# 140629_AriloTX_REV2_0_0.net
KiCad netlist of a schematic drawn in EAGLE
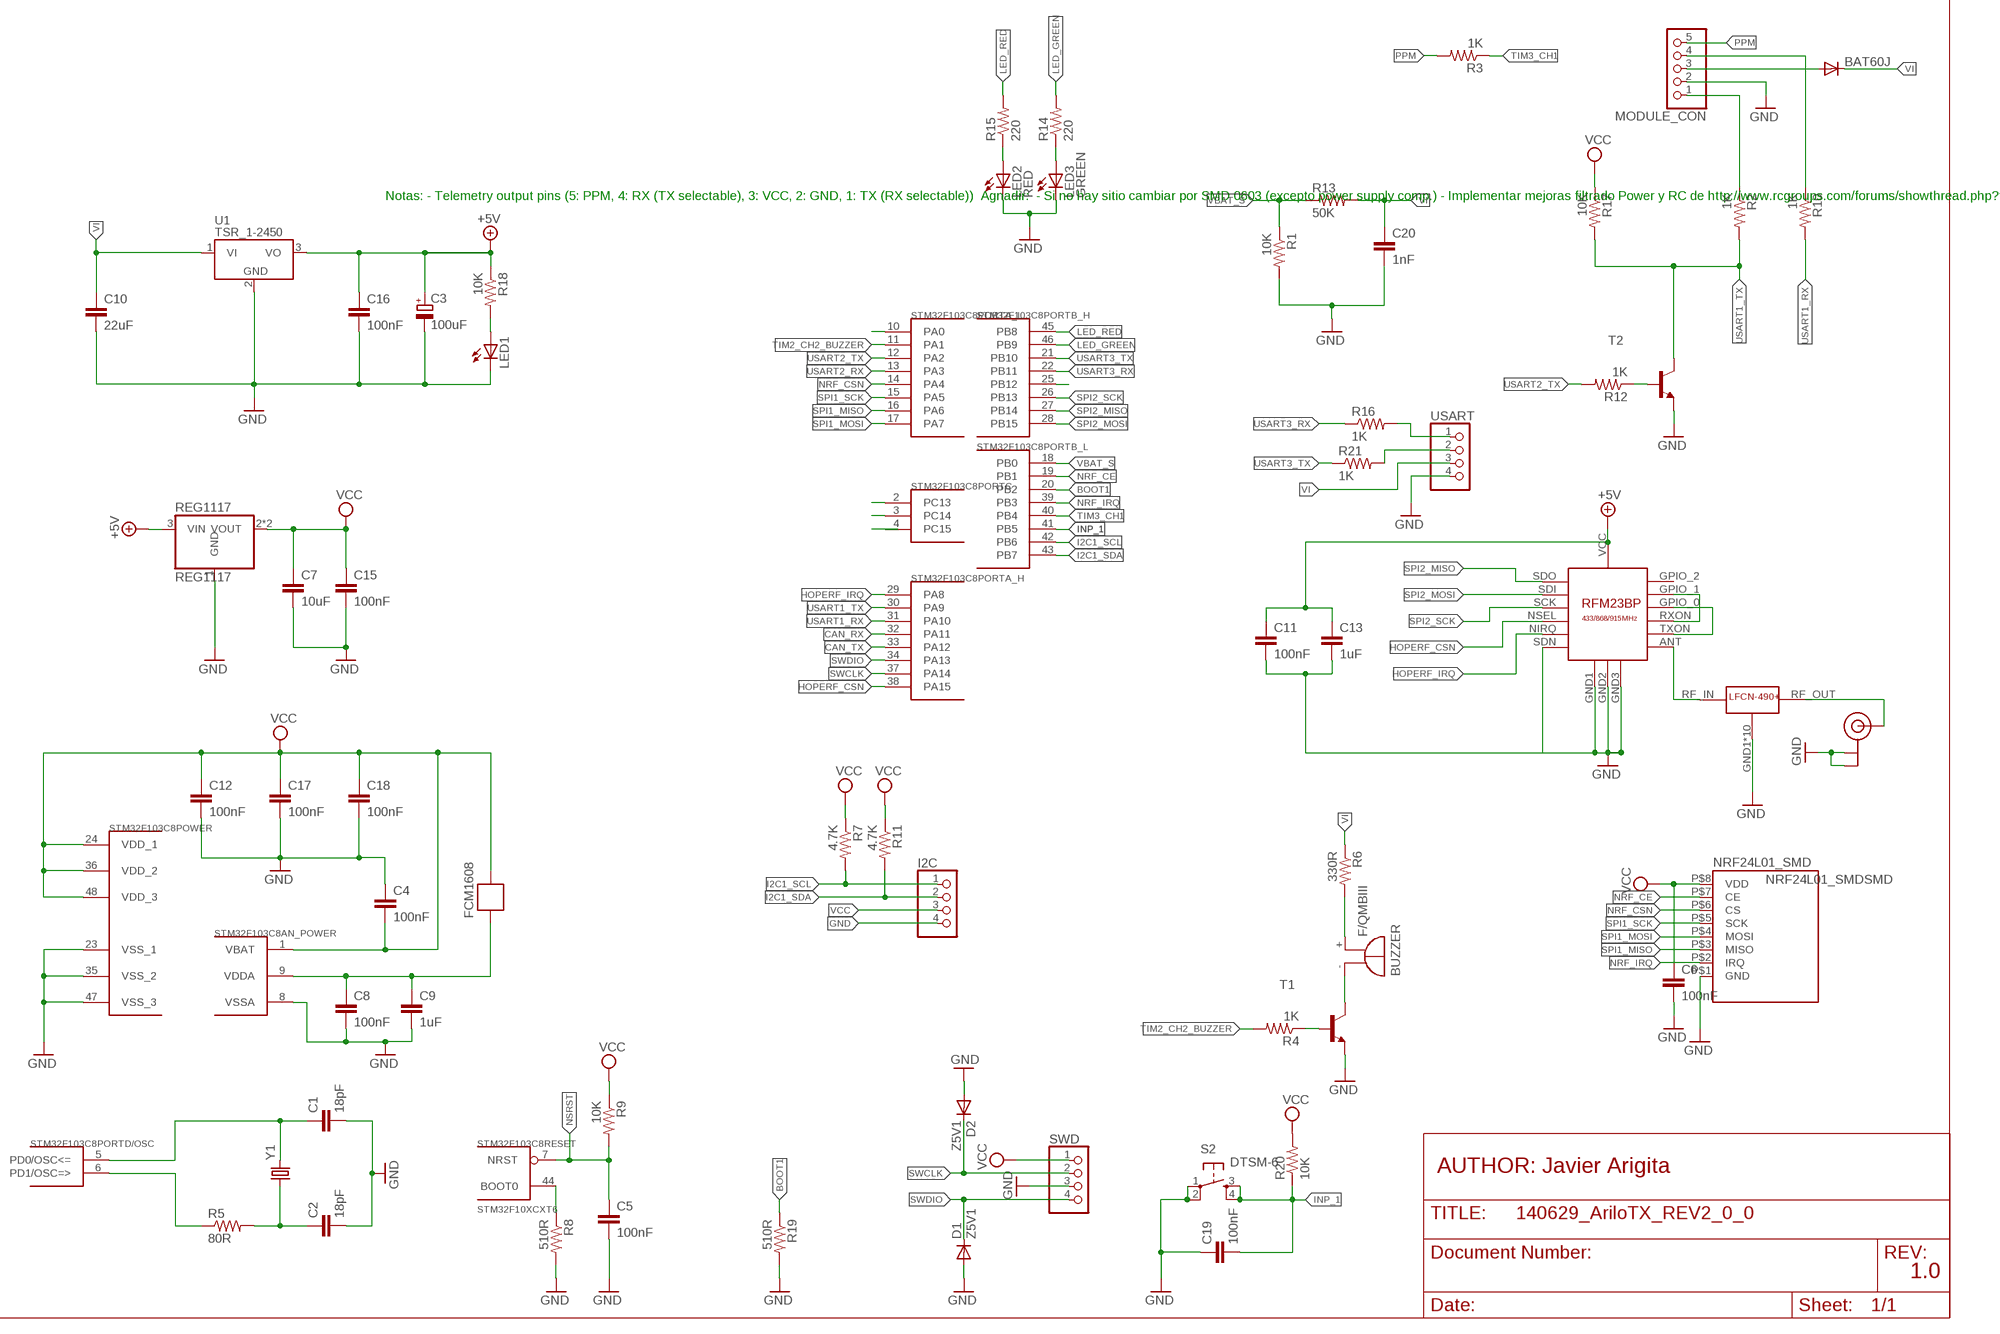
[diagram p0: schematic, sheet 1, part 1 of 2]
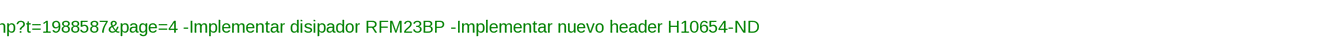
[diagram p1: schematic, sheet 1, part 2 of 2]

(export (version "E")
  (design (tool "Eeschema 10.0.6"))
  (components
    (comp (ref "BAT60J")
      (value "DIODE-SOD323-R")
      (footprint "eagle-import:SOD323-R")
      (libsource (lib "eagle-import") (part "DIODE-SOD323-R"))
    )
    (comp (ref "BUZZER")
      (value "F/QMBIII")
      (footprint "eagle-import:F_QMBIII")
      (libsource (lib "eagle-import") (part "F/QMBIII"))
    )
    (comp (ref "C1")
      (value "18pF")
      (footprint "eagle-import:C0805")
      (libsource (lib "eagle-import") (part "C-EUC0805"))
    )
    (comp (ref "C2")
      (value "18pF")
      (footprint "eagle-import:C0805")
      (libsource (lib "eagle-import") (part "C-EUC0805"))
    )
    (comp (ref "C3")
      (value "100uF")
      (footprint "eagle-import:SMC_B")
      (libsource (lib "eagle-import") (part "CPOL-EUSMCB"))
    )
    (comp (ref "C4")
      (value "100nF")
      (footprint "eagle-import:C0805")
      (libsource (lib "eagle-import") (part "C-EUC0805"))
    )
    (comp (ref "C5")
      (value "100nF")
      (footprint "eagle-import:C0805")
      (libsource (lib "eagle-import") (part "C-EUC0805"))
    )
    (comp (ref "C6")
      (value "100nF")
      (footprint "eagle-import:C0805")
      (libsource (lib "eagle-import") (part "C-EUC0805"))
    )
    (comp (ref "C7")
      (value "10uF")
      (footprint "eagle-import:C0805")
      (libsource (lib "eagle-import") (part "C-EUC0805"))
    )
    (comp (ref "C8")
      (value "100nF")
      (footprint "eagle-import:C0805")
      (libsource (lib "eagle-import") (part "C-EUC0805"))
    )
    (comp (ref "C9")
      (value "1uF")
      (footprint "eagle-import:C3216")
      (libsource (lib "eagle-import") (part "resistor_C-EUC3216"))
    )
    (comp (ref "C10")
      (value "22uF")
      (footprint "eagle-import:C3216")
      (libsource (lib "eagle-import") (part "resistor_C-EUC3216"))
    )
    (comp (ref "C11")
      (value "100nF")
      (footprint "eagle-import:C0805")
      (libsource (lib "eagle-import") (part "C-EUC0805"))
    )
    (comp (ref "C12")
      (value "100nF")
      (footprint "eagle-import:C0805")
      (libsource (lib "eagle-import") (part "C-EUC0805"))
    )
    (comp (ref "C13")
      (value "1uF")
      (footprint "eagle-import:C3216")
      (libsource (lib "eagle-import") (part "resistor_C-EUC3216"))
    )
    (comp (ref "C15")
      (value "100nF")
      (footprint "eagle-import:C0805")
      (libsource (lib "eagle-import") (part "C-EUC0805"))
    )
    (comp (ref "C16")
      (value "100nF")
      (footprint "eagle-import:C0805")
      (libsource (lib "eagle-import") (part "C-EUC0805"))
    )
    (comp (ref "C17")
      (value "100nF")
      (footprint "eagle-import:C0805")
      (libsource (lib "eagle-import") (part "C-EUC0805"))
    )
    (comp (ref "C18")
      (value "100nF")
      (footprint "eagle-import:C0805")
      (libsource (lib "eagle-import") (part "C-EUC0805"))
    )
    (comp (ref "C19")
      (value "100nF")
      (footprint "eagle-import:C0805")
      (libsource (lib "eagle-import") (part "C-EUC0805"))
    )
    (comp (ref "C20")
      (value "1nF")
      (footprint "eagle-import:C0805")
      (libsource (lib "eagle-import") (part "C-EUC0805"))
    )
    (comp (ref "D1")
      (value "Z5V1")
      (footprint "eagle-import:SOD323-R")
      (libsource (lib "eagle-import") (part "DIODE-SOD323-R"))
    )
    (comp (ref "D2")
      (value "Z5V1")
      (footprint "eagle-import:SOD323-R")
      (libsource (lib "eagle-import") (part "DIODE-SOD323-R"))
    )
    (comp (ref "FCM1608")
      (value "FERRITE-BEAD")
      (footprint "eagle-import:R0603")
      (libsource (lib "eagle-import") (part "FERRITE-BEAD"))
    )
    (comp (ref "I2C")
      (value "PINHD-1X4")
      (footprint "eagle-import:1X04")
      (libsource (lib "eagle-import") (part "PINHD-1X4"))
    )
    (comp (ref "LED1")
      (value "LED0805")
      (footprint "eagle-import:CHIPLED_0805")
      (libsource (lib "eagle-import") (part "LED0805"))
    )
    (comp (ref "LED2")
      (value "RED")
      (footprint "eagle-import:CHIP-LED0805")
      (libsource (lib "eagle-import") (part "LEDCHIP-LED0805"))
    )
    (comp (ref "LED3")
      (value "GREEN")
      (footprint "eagle-import:CHIP-LED0805")
      (libsource (lib "eagle-import") (part "LEDCHIP-LED0805"))
    )
    (comp (ref "MODULE_CON")
      (value "PINHD-1X5")
      (footprint "eagle-import:1X05")
      (libsource (lib "eagle-import") (part "PINHD-1X5"))
    )
    (comp (ref "NRF24L01_SMD")
      (value "NRF24L01_SMDSMD")
      (footprint "eagle-import:NRF24L01_SMD")
      (libsource (lib "eagle-import") (part "NRF24L01_SMDSMD"))
    )
    (comp (ref "R1")
      (value "10K")
      (footprint "eagle-import:R0805")
      (libsource (lib "eagle-import") (part "RESISTOR0805"))
    )
    (comp (ref "R2")
      (value "1K")
      (footprint "eagle-import:R0805")
      (libsource (lib "eagle-import") (part "RESISTOR0805"))
    )
    (comp (ref "R3")
      (value "1K")
      (footprint "eagle-import:R0805")
      (libsource (lib "eagle-import") (part "RESISTOR0805"))
    )
    (comp (ref "R4")
      (value "1K")
      (footprint "eagle-import:R0805")
      (libsource (lib "eagle-import") (part "RESISTOR0805"))
    )
    (comp (ref "R5")
      (value "80R")
      (footprint "eagle-import:R0805")
      (libsource (lib "eagle-import") (part "RESISTOR0805"))
    )
    (comp (ref "R6")
      (value "330R")
      (footprint "eagle-import:R0805")
      (libsource (lib "eagle-import") (part "RESISTOR0805"))
    )
    (comp (ref "R7")
      (value "4.7K")
      (footprint "eagle-import:R0805")
      (libsource (lib "eagle-import") (part "RESISTOR0805"))
    )
    (comp (ref "R8")
      (value "510R")
      (footprint "eagle-import:R0805")
      (libsource (lib "eagle-import") (part "RESISTOR0805"))
    )
    (comp (ref "R9")
      (value "10K")
      (footprint "eagle-import:R0805")
      (libsource (lib "eagle-import") (part "RESISTOR0805"))
    )
    (comp (ref "R10")
      (value "1K")
      (footprint "eagle-import:R0805")
      (libsource (lib "eagle-import") (part "RESISTOR0805"))
    )
    (comp (ref "R11")
      (value "4.7K")
      (footprint "eagle-import:R0805")
      (libsource (lib "eagle-import") (part "RESISTOR0805"))
    )
    (comp (ref "R12")
      (value "1K")
      (footprint "eagle-import:R0805")
      (libsource (lib "eagle-import") (part "RESISTOR0805"))
    )
    (comp (ref "R13")
      (value "50K")
      (footprint "eagle-import:R0805")
      (libsource (lib "eagle-import") (part "RESISTOR0805"))
    )
    (comp (ref "R14")
      (value "220")
      (footprint "eagle-import:R0805")
      (libsource (lib "eagle-import") (part "RESISTOR0805"))
    )
    (comp (ref "R15")
      (value "220")
      (footprint "eagle-import:R0805")
      (libsource (lib "eagle-import") (part "RESISTOR0805"))
    )
    (comp (ref "R16")
      (value "1K")
      (footprint "eagle-import:R0805")
      (libsource (lib "eagle-import") (part "RESISTOR0805"))
    )
    (comp (ref "R17")
      (value "10K")
      (footprint "eagle-import:R0805")
      (libsource (lib "eagle-import") (part "RESISTOR0805"))
    )
    (comp (ref "R18")
      (value "10K")
      (footprint "eagle-import:R0805")
      (libsource (lib "eagle-import") (part "RESISTOR0805"))
    )
    (comp (ref "R19")
      (value "510R")
      (footprint "eagle-import:R0805")
      (libsource (lib "eagle-import") (part "RESISTOR0805"))
    )
    (comp (ref "R20")
      (value "10K")
      (footprint "eagle-import:R0805")
      (libsource (lib "eagle-import") (part "RESISTOR0805"))
    )
    (comp (ref "R21")
      (value "1K")
      (footprint "eagle-import:R0805")
      (libsource (lib "eagle-import") (part "RESISTOR0805"))
    )
    (comp (ref "REG1117")
      (value "REG1117")
      (footprint "eagle-import:SOT223")
      (libsource (lib "eagle-import") (part "REG1117"))
    )
    (comp (ref "S2")
      (value "DTSM-6")
      (footprint "eagle-import:DTSM-6")
      (libsource (lib "eagle-import") (part "DTSM-6"))
    )
    (comp (ref "STM32F103C8")
      (value "STM32F10XCXT6")
      (footprint "eagle-import:TQFP48")
      (libsource (lib "eagle-import") (part "STM32F10XCXT6"))
    )
    (comp (ref "SWD")
      (value "PINHD-1X4")
      (footprint "eagle-import:1X04")
      (libsource (lib "eagle-import") (part "PINHD-1X4"))
    )
    (comp (ref "T1")
      (value "BC848-NPN-SOT23-BEC")
      (footprint "eagle-import:SOT23-BEC")
      (libsource (lib "eagle-import") (part "-NPN-SOT23-BECBC848"))
    )
    (comp (ref "T2")
      (value "BC848-NPN-SOT23-BEC")
      (footprint "eagle-import:SOT23-BEC")
      (libsource (lib "eagle-import") (part "-NPN-SOT23-BECBC848"))
    )
    (comp (ref "U$1")
      (value "RFM23BP")
      (footprint "eagle-import:RFM23BP")
      (libsource (lib "eagle-import") (part "RFM23BP"))
    )
    (comp (ref "U$2")
      (value "LFCN490+")
      (footprint "eagle-import:LFCN490+")
      (libsource (lib "eagle-import") (part "LFCN490+"))
    )
    (comp (ref "U$3")
      (value "U.FL")
      (footprint "eagle-import:U.FL")
      (libsource (lib "eagle-import") (part "U.FL"))
    )
    (comp (ref "U1")
      (value "TSR_1-2450")
      (footprint "eagle-import:TSR-1")
      (libsource (lib "eagle-import") (part "TSR_1-2450"))
    )
    (comp (ref "USART")
      (value "PINHD-1X4")
      (footprint "eagle-import:1X04")
      (libsource (lib "eagle-import") (part "PINHD-1X4"))
    )
    (comp (ref "Y1")
      (value "CRYSTAL5X3")
      (footprint "eagle-import:CRYSTAL-SMD-5X3")
      (libsource (lib "eagle-import") (part "CRYSTAL5X3"))
    )
  )
  (nets
    (net (code "1") (name "+5V") (class "Default")
      (node (ref "C11") (pin "1") (pinfunction "1_1") (pintype "passive"))
      (node (ref "C13") (pin "1") (pinfunction "1_1") (pintype "passive"))
      (node (ref "C16") (pin "1") (pinfunction "1_1") (pintype "passive"))
      (node (ref "C3") (pin "+") (pinfunction "+_+") (pintype "passive"))
      (node (ref "R18") (pin "1") (pinfunction "1_1") (pintype "passive"))
      (node (ref "REG1117") (pin "3") (pinfunction "VIN_3") (pintype "input"))
      (node (ref "U$1") (pin "VCC") (pinfunction "VCC_VCC") (pintype "power_in"))
      (node (ref "U1") (pin "3") (pinfunction "VO_3") (pintype "power_in"))
    )
    (net (code "2") (name "BOOT1") (class "Default")
      (node (ref "R19") (pin "1") (pinfunction "1_1") (pintype "passive"))
      (node (ref "STM32F103C8") (pin "20") (pinfunction "PB2_20") (pintype "bidirectional"))
    )
    (net (code "3") (name "CAN_RX") (class "Default")
      (node (ref "STM32F103C8") (pin "32") (pinfunction "PA11_32") (pintype "bidirectional"))
    )
    (net (code "4") (name "CAN_TX") (class "Default")
      (node (ref "STM32F103C8") (pin "33") (pinfunction "PA12_33") (pintype "bidirectional"))
    )
    (net (code "5") (name "GND") (class "Default")
      (node (ref "C1") (pin "2") (pinfunction "2_2") (pintype "passive"))
      (node (ref "C10") (pin "2") (pinfunction "2_2") (pintype "passive"))
      (node (ref "C11") (pin "2") (pinfunction "2_2") (pintype "passive"))
      (node (ref "C12") (pin "2") (pinfunction "2_2") (pintype "passive"))
      (node (ref "C13") (pin "2") (pinfunction "2_2") (pintype "passive"))
      (node (ref "C15") (pin "2") (pinfunction "2_2") (pintype "passive"))
      (node (ref "C16") (pin "2") (pinfunction "2_2") (pintype "passive"))
      (node (ref "C17") (pin "2") (pinfunction "2_2") (pintype "passive"))
      (node (ref "C18") (pin "2") (pinfunction "2_2") (pintype "passive"))
      (node (ref "C19") (pin "1") (pinfunction "1_1") (pintype "passive"))
      (node (ref "C2") (pin "2") (pinfunction "2_2") (pintype "passive"))
      (node (ref "C20") (pin "2") (pinfunction "2_2") (pintype "passive"))
      (node (ref "C3") (pin "-") (pinfunction "-_-") (pintype "passive"))
      (node (ref "C4") (pin "1") (pinfunction "1_1") (pintype "passive"))
      (node (ref "C5") (pin "2") (pinfunction "2_2") (pintype "passive"))
      (node (ref "C6") (pin "2") (pinfunction "2_2") (pintype "passive"))
      (node (ref "C7") (pin "2") (pinfunction "2_2") (pintype "passive"))
      (node (ref "C8") (pin "2") (pinfunction "2_2") (pintype "passive"))
      (node (ref "C9") (pin "2") (pinfunction "2_2") (pintype "passive"))
      (node (ref "D1") (pin "A") (pinfunction "A_A") (pintype "passive"))
      (node (ref "D2") (pin "A") (pinfunction "A_A") (pintype "passive"))
      (node (ref "I2C") (pin "4") (pinfunction "4_4") (pintype "passive"))
      (node (ref "LED1") (pin "C") (pinfunction "C_C") (pintype "passive"))
      (node (ref "LED2") (pin "C") (pinfunction "C_C") (pintype "passive"))
      (node (ref "LED3") (pin "C") (pinfunction "C_C") (pintype "passive"))
      (node (ref "MODULE_CON") (pin "2") (pinfunction "2_2") (pintype "passive"))
      (node (ref "NRF24L01_SMD") (pin "P$1") (pinfunction "GND_P$1") (pintype "power_in"))
      (node (ref "R1") (pin "2") (pinfunction "2_2") (pintype "passive"))
      (node (ref "R19") (pin "2") (pinfunction "2_2") (pintype "passive"))
      (node (ref "R8") (pin "2") (pinfunction "2_2") (pintype "passive"))
      (node (ref "REG1117") (pin "1") (pinfunction "GND_1") (pintype "power_in"))
      (node (ref "S2") (pin "1") (pinfunction "1_1") (pintype "passive"))
      (node (ref "S2") (pin "2") (pinfunction "2_2") (pintype "passive"))
      (node (ref "STM32F103C8") (pin "23") (pinfunction "VSS_1_23") (pintype "power_in"))
      (node (ref "STM32F103C8") (pin "35") (pinfunction "VSS_2_35") (pintype "power_in"))
      (node (ref "STM32F103C8") (pin "47") (pinfunction "VSS_3_47") (pintype "power_in"))
      (node (ref "STM32F103C8") (pin "8") (pinfunction "VSSA_8") (pintype "power_in"))
      (node (ref "SWD") (pin "3") (pinfunction "3_3") (pintype "passive"))
      (node (ref "T1") (pin "E") (pinfunction "E_E") (pintype "passive"))
      (node (ref "T2") (pin "E") (pinfunction "E_E") (pintype "passive"))
      (node (ref "U$1") (pin "GND1") (pinfunction "GND1_GND1") (pintype "power_in"))
      (node (ref "U$1") (pin "GND2") (pinfunction "GND2_GND2") (pintype "power_in"))
      (node (ref "U$1") (pin "GND3") (pinfunction "GND3_GND3") (pintype "power_in"))
      (node (ref "U$1") (pin "SDN") (pinfunction "SDN_SDN") (pintype "bidirectional"))
      (node (ref "U$2") (pin "GND1") (pinfunction "GND_GND1") (pintype "bidirectional"))
      (node (ref "U$2") (pin "GND10") (pinfunction "GND_GND10") (pintype "bidirectional"))
      (node (ref "U$2") (pin "GND2") (pinfunction "GND_GND2") (pintype "bidirectional"))
      (node (ref "U$2") (pin "GND3") (pinfunction "GND_GND3") (pintype "bidirectional"))
      (node (ref "U$2") (pin "GND4") (pinfunction "GND_GND4") (pintype "bidirectional"))
      (node (ref "U$2") (pin "GND5") (pinfunction "GND_GND5") (pintype "bidirectional"))
      (node (ref "U$2") (pin "GND6") (pinfunction "GND_GND6") (pintype "bidirectional"))
      (node (ref "U$2") (pin "GND7") (pinfunction "GND_GND7") (pintype "bidirectional"))
      (node (ref "U$2") (pin "GND8") (pinfunction "GND_GND8") (pintype "bidirectional"))
      (node (ref "U$2") (pin "GND9") (pinfunction "GND_GND9") (pintype "bidirectional"))
      (node (ref "U$3") (pin "P$1") (pinfunction "GND_P$1") (pintype "bidirectional"))
      (node (ref "U$3") (pin "P$2") (pinfunction "GND_P$2") (pintype "bidirectional"))
      (node (ref "U1") (pin "2") (pinfunction "GND_2") (pintype "power_in"))
      (node (ref "USART") (pin "4") (pinfunction "4_4") (pintype "passive"))
    )
    (net (code "6") (name "HOPERF_CSN") (class "Default")
      (node (ref "STM32F103C8") (pin "38") (pinfunction "PA15_38") (pintype "bidirectional"))
      (node (ref "U$1") (pin "NSEL") (pinfunction "NSEL_NSEL") (pintype "bidirectional"))
    )
    (net (code "7") (name "HOPERF_IRQ") (class "Default")
      (node (ref "STM32F103C8") (pin "29") (pinfunction "PA8_29") (pintype "bidirectional"))
      (node (ref "U$1") (pin "NIRQ") (pinfunction "NIRQ_NIRQ") (pintype "bidirectional"))
    )
    (net (code "8") (name "I2C1_SCL") (class "Default")
      (node (ref "I2C") (pin "1") (pinfunction "1_1") (pintype "passive"))
      (node (ref "R7") (pin "2") (pinfunction "2_2") (pintype "passive"))
      (node (ref "STM32F103C8") (pin "42") (pinfunction "PB6_42") (pintype "bidirectional"))
    )
    (net (code "9") (name "I2C1_SDA") (class "Default")
      (node (ref "I2C") (pin "2") (pinfunction "2_2") (pintype "passive"))
      (node (ref "R11") (pin "2") (pinfunction "2_2") (pintype "passive"))
      (node (ref "STM32F103C8") (pin "43") (pinfunction "PB7_43") (pintype "bidirectional"))
    )
    (net (code "10") (name "INP_1") (class "Default")
      (node (ref "C19") (pin "2") (pinfunction "2_2") (pintype "passive"))
      (node (ref "R20") (pin "1") (pinfunction "1_1") (pintype "passive"))
      (node (ref "S2") (pin "3") (pinfunction "3_3") (pintype "passive"))
      (node (ref "S2") (pin "4") (pinfunction "4_4") (pintype "passive"))
      (node (ref "STM32F103C8") (pin "41") (pinfunction "PB5_41") (pintype "bidirectional"))
    )
    (net (code "11") (name "LED_GREEN") (class "Default")
      (node (ref "R14") (pin "2") (pinfunction "2_2") (pintype "passive"))
      (node (ref "STM32F103C8") (pin "46") (pinfunction "PB9_46") (pintype "bidirectional"))
    )
    (net (code "12") (name "LED_RED") (class "Default")
      (node (ref "R15") (pin "2") (pinfunction "2_2") (pintype "passive"))
      (node (ref "STM32F103C8") (pin "45") (pinfunction "PB8_45") (pintype "bidirectional"))
    )
    (net (code "13") (name "NRF_CE") (class "Default")
      (node (ref "NRF24L01_SMD") (pin "P$7") (pinfunction "CE_P$7") (pintype "input"))
      (node (ref "STM32F103C8") (pin "19") (pinfunction "PB1_19") (pintype "bidirectional"))
    )
    (net (code "14") (name "NRF_CSN") (class "Default")
      (node (ref "NRF24L01_SMD") (pin "P$6") (pinfunction "CS_P$6") (pintype "input"))
      (node (ref "STM32F103C8") (pin "14") (pinfunction "PA4_14") (pintype "bidirectional"))
    )
    (net (code "15") (name "NRF_IRQ") (class "Default")
      (node (ref "NRF24L01_SMD") (pin "P$2") (pinfunction "IRQ_P$2") (pintype "output"))
      (node (ref "STM32F103C8") (pin "39") (pinfunction "PB3_39") (pintype "bidirectional"))
    )
    (net (code "16") (name "NSRST") (class "Default")
      (node (ref "C5") (pin "1") (pinfunction "1_1") (pintype "passive"))
      (node (ref "R9") (pin "2") (pinfunction "2_2") (pintype "passive"))
      (node (ref "STM32F103C8") (pin "7") (pinfunction "NRST_7") (pintype "input"))
    )
    (net (code "17") (name "Net-(BAT60J-PadA)") (class "Default")
      (node (ref "BAT60J") (pin "A") (pinfunction "A_A") (pintype "passive"))
      (node (ref "MODULE_CON") (pin "3") (pinfunction "3_3") (pintype "passive"))
    )
    (net (code "18") (name "Net-(BUZZER-+)") (class "Default")
      (node (ref "BUZZER") (pin "-") (pinfunction "+_-") (pintype "passive"))
      (node (ref "T1") (pin "C") (pinfunction "C_C") (pintype "passive"))
    )
    (net (code "19") (name "Net-(BUZZER--)") (class "Default")
      (node (ref "BUZZER") (pin "+") (pinfunction "-_+") (pintype "passive"))
      (node (ref "R6") (pin "2") (pinfunction "2_2") (pintype "passive"))
    )
    (net (code "20") (name "Net-(C2-Pad1)") (class "Default")
      (node (ref "C2") (pin "1") (pinfunction "1_1") (pintype "passive"))
      (node (ref "R5") (pin "2") (pinfunction "2_2") (pintype "passive"))
      (node (ref "Y1") (pin "1") (pinfunction "1_1") (pintype "passive"))
    )
    (net (code "21") (name "Net-(FCM1608-P$2)") (class "Default")
      (node (ref "C8") (pin "1") (pinfunction "1_1") (pintype "passive"))
      (node (ref "C9") (pin "1") (pinfunction "1_1") (pintype "passive"))
      (node (ref "FCM1608") (pin "2") (pinfunction "P$2_2") (pintype "bidirectional"))
      (node (ref "STM32F103C8") (pin "9") (pinfunction "VDDA_9") (pintype "power_in"))
    )
    (net (code "22") (name "Net-(LED1-PadA)") (class "Default")
      (node (ref "LED1") (pin "A") (pinfunction "A_A") (pintype "passive"))
      (node (ref "R18") (pin "2") (pinfunction "2_2") (pintype "passive"))
    )
    (net (code "23") (name "Net-(LED2-PadA)") (class "Default")
      (node (ref "LED2") (pin "A") (pinfunction "A_A") (pintype "passive"))
      (node (ref "R15") (pin "1") (pinfunction "1_1") (pintype "passive"))
    )
    (net (code "24") (name "Net-(LED3-PadA)") (class "Default")
      (node (ref "LED3") (pin "A") (pinfunction "A_A") (pintype "passive"))
      (node (ref "R14") (pin "1") (pinfunction "1_1") (pintype "passive"))
    )
    (net (code "25") (name "Net-(MODULE_CON-Pad1)") (class "Default")
      (node (ref "MODULE_CON") (pin "1") (pinfunction "1_1") (pintype "passive"))
      (node (ref "R2") (pin "1") (pinfunction "1_1") (pintype "passive"))
    )
    (net (code "26") (name "Net-(MODULE_CON-Pad4)") (class "Default")
      (node (ref "MODULE_CON") (pin "4") (pinfunction "4_4") (pintype "passive"))
      (node (ref "R10") (pin "1") (pinfunction "1_1") (pintype "passive"))
    )
    (net (code "27") (name "Net-(R4-Pad1)") (class "Default")
      (node (ref "R4") (pin "1") (pinfunction "1_1") (pintype "passive"))
      (node (ref "T1") (pin "B") (pinfunction "B_B") (pintype "passive"))
    )
    (net (code "28") (name "Net-(R12-Pad1)") (class "Default")
      (node (ref "R12") (pin "1") (pinfunction "1_1") (pintype "passive"))
      (node (ref "T2") (pin "B") (pinfunction "B_B") (pintype "passive"))
    )
    (net (code "29") (name "Net-(R16-Pad2)") (class "Default")
      (node (ref "R16") (pin "2") (pinfunction "2_2") (pintype "passive"))
      (node (ref "USART") (pin "1") (pinfunction "1_1") (pintype "passive"))
    )
    (net (code "30") (name "Net-(R21-Pad2)") (class "Default")
      (node (ref "R21") (pin "2") (pinfunction "2_2") (pintype "passive"))
      (node (ref "USART") (pin "2") (pinfunction "2_2") (pintype "passive"))
    )
    (net (code "31") (name "Net-(STM32F103C8G-PD0{slash}OSC<=)") (class "Default")
      (node (ref "C1") (pin "1") (pinfunction "1_1") (pintype "passive"))
      (node (ref "STM32F103C8") (pin "5") (pinfunction "PD0/OSC<=_5") (pintype "bidirectional"))
      (node (ref "Y1") (pin "3") (pinfunction "2_3") (pintype "passive"))
    )
    (net (code "32") (name "Net-(STM32F103C8G-PD1{slash}OSC=>)") (class "Default")
      (node (ref "R5") (pin "1") (pinfunction "1_1") (pintype "passive"))
      (node (ref "STM32F103C8") (pin "6") (pinfunction "PD1/OSC=>_6") (pintype "bidirectional"))
    )
    (net (code "33") (name "Net-(STM32F103C8I-BOOT0)") (class "Default")
      (node (ref "R8") (pin "1") (pinfunction "1_1") (pintype "passive"))
      (node (ref "STM32F103C8") (pin "44") (pinfunction "BOOT0_44") (pintype "input"))
    )
    (net (code "34") (name "Net-(U$1-PadGPIO_0)") (class "Default")
      (node (ref "U$1") (pin "GPIO_0") (pinfunction "GPIO_0_GPIO_0") (pintype "bidirectional"))
      (node (ref "U$1") (pin "TXON") (pinfunction "TXON_TXON") (pintype "bidirectional"))
    )
    (net (code "35") (name "Net-(U$1-PadGPIO_1)") (class "Default")
      (node (ref "U$1") (pin "GPIO_1") (pinfunction "GPIO_1_GPIO_1") (pintype "bidirectional"))
      (node (ref "U$1") (pin "RXON") (pinfunction "RXON_RXON") (pintype "bidirectional"))
    )
    (net (code "36") (name "Net-(U$2-RF_INP)") (class "Default")
      (node (ref "U$1") (pin "ANT") (pinfunction "ANT_ANT") (pintype "bidirectional"))
      (node (ref "U$2") (pin "RF_IN") (pinfunction "RF_INP_RF_IN") (pintype "bidirectional"))
    )
    (net (code "37") (name "Net-(U$2-RF_OUTP)") (class "Default")
      (node (ref "U$2") (pin "RF_OUT") (pinfunction "RF_OUTP_RF_OUT") (pintype "bidirectional"))
      (node (ref "U$3") (pin "P$3") (pinfunction "SIGNAL_P$3") (pintype "bidirectional"))
    )
    (net (code "38") (name "PPM") (class "Default")
      (node (ref "MODULE_CON") (pin "5") (pinfunction "5_5") (pintype "passive"))
      (node (ref "R3") (pin "2") (pinfunction "2_2") (pintype "passive"))
    )
    (net (code "39") (name "SPI1_MISO") (class "Default")
      (node (ref "NRF24L01_SMD") (pin "P$3") (pinfunction "MISO_P$3") (pintype "output"))
      (node (ref "STM32F103C8") (pin "16") (pinfunction "PA6_16") (pintype "bidirectional"))
    )
    (net (code "40") (name "SPI1_MOSI") (class "Default")
      (node (ref "NRF24L01_SMD") (pin "P$4") (pinfunction "MOSI_P$4") (pintype "input"))
      (node (ref "STM32F103C8") (pin "17") (pinfunction "PA7_17") (pintype "bidirectional"))
    )
    (net (code "41") (name "SPI1_SCK") (class "Default")
      (node (ref "NRF24L01_SMD") (pin "P$5") (pinfunction "SCK_P$5") (pintype "input"))
      (node (ref "STM32F103C8") (pin "15") (pinfunction "PA5_15") (pintype "bidirectional"))
    )
    (net (code "42") (name "SPI2_MISO") (class "Default")
      (node (ref "STM32F103C8") (pin "27") (pinfunction "PB14_27") (pintype "bidirectional"))
      (node (ref "U$1") (pin "SDO") (pinfunction "SDO_SDO") (pintype "bidirectional"))
    )
    (net (code "43") (name "SPI2_MOSI") (class "Default")
      (node (ref "STM32F103C8") (pin "28") (pinfunction "PB15_28") (pintype "bidirectional"))
      (node (ref "U$1") (pin "SDI") (pinfunction "SDI_SDI") (pintype "bidirectional"))
    )
    (net (code "44") (name "SPI2_SCK") (class "Default")
      (node (ref "STM32F103C8") (pin "26") (pinfunction "PB13_26") (pintype "bidirectional"))
      (node (ref "U$1") (pin "SCK") (pinfunction "SCK_SCK") (pintype "bidirectional"))
    )
    (net (code "45") (name "SWCLK") (class "Default")
      (node (ref "D2") (pin "C") (pinfunction "C_C") (pintype "passive"))
      (node (ref "STM32F103C8") (pin "37") (pinfunction "PA14_37") (pintype "bidirectional"))
      (node (ref "SWD") (pin "2") (pinfunction "2_2") (pintype "passive"))
    )
    (net (code "46") (name "SWDIO") (class "Default")
      (node (ref "D1") (pin "C") (pinfunction "C_C") (pintype "passive"))
      (node (ref "STM32F103C8") (pin "34") (pinfunction "PA13_34") (pintype "bidirectional"))
      (node (ref "SWD") (pin "4") (pinfunction "4_4") (pintype "passive"))
    )
    (net (code "47") (name "TIM2_CH2_BUZZER") (class "Default")
      (node (ref "R4") (pin "2") (pinfunction "2_2") (pintype "passive"))
      (node (ref "STM32F103C8") (pin "11") (pinfunction "PA1_11") (pintype "bidirectional"))
    )
    (net (code "48") (name "TIM3_CH1") (class "Default")
      (node (ref "R3") (pin "1") (pinfunction "1_1") (pintype "passive"))
      (node (ref "STM32F103C8") (pin "40") (pinfunction "PB4_40") (pintype "bidirectional"))
    )
    (net (code "49") (name "USART1_RX") (class "Default")
      (node (ref "R10") (pin "2") (pinfunction "2_2") (pintype "passive"))
      (node (ref "STM32F103C8") (pin "31") (pinfunction "PA10_31") (pintype "bidirectional"))
    )
    (net (code "50") (name "USART1_TX") (class "Default")
      (node (ref "R17") (pin "2") (pinfunction "2_2") (pintype "passive"))
      (node (ref "R2") (pin "2") (pinfunction "2_2") (pintype "passive"))
      (node (ref "STM32F103C8") (pin "30") (pinfunction "PA9_30") (pintype "bidirectional"))
      (node (ref "T2") (pin "C") (pinfunction "C_C") (pintype "passive"))
    )
    (net (code "51") (name "USART2_RX") (class "Default")
      (node (ref "STM32F103C8") (pin "13") (pinfunction "PA3_13") (pintype "bidirectional"))
    )
    (net (code "52") (name "USART2_TX") (class "Default")
      (node (ref "R12") (pin "2") (pinfunction "2_2") (pintype "passive"))
      (node (ref "STM32F103C8") (pin "12") (pinfunction "PA2_12") (pintype "bidirectional"))
    )
    (net (code "53") (name "USART3_RX") (class "Default")
      (node (ref "R16") (pin "1") (pinfunction "1_1") (pintype "passive"))
      (node (ref "STM32F103C8") (pin "22") (pinfunction "PB11_22") (pintype "bidirectional"))
    )
    (net (code "54") (name "USART3_TX") (class "Default")
      (node (ref "R21") (pin "1") (pinfunction "1_1") (pintype "passive"))
      (node (ref "STM32F103C8") (pin "21") (pinfunction "PB10_21") (pintype "bidirectional"))
    )
    (net (code "55") (name "VBAT_S") (class "Default")
      (node (ref "R1") (pin "1") (pinfunction "1_1") (pintype "passive"))
      (node (ref "R13") (pin "1") (pinfunction "1_1") (pintype "passive"))
      (node (ref "STM32F103C8") (pin "18") (pinfunction "PB0_18") (pintype "bidirectional"))
    )
    (net (code "56") (name "VCC") (class "Default")
      (node (ref "C12") (pin "1") (pinfunction "1_1") (pintype "passive"))
      (node (ref "C15") (pin "1") (pinfunction "1_1") (pintype "passive"))
      (node (ref "C17") (pin "1") (pinfunction "1_1") (pintype "passive"))
      (node (ref "C18") (pin "1") (pinfunction "1_1") (pintype "passive"))
      (node (ref "C4") (pin "2") (pinfunction "2_2") (pintype "passive"))
      (node (ref "C6") (pin "1") (pinfunction "1_1") (pintype "passive"))
      (node (ref "C7") (pin "1") (pinfunction "1_1") (pintype "passive"))
      (node (ref "FCM1608") (pin "1") (pinfunction "P$1_1") (pintype "bidirectional"))
      (node (ref "I2C") (pin "3") (pinfunction "3_3") (pintype "passive"))
      (node (ref "NRF24L01_SMD") (pin "P$8") (pinfunction "VDD_P$8") (pintype "bidirectional"))
      (node (ref "R11") (pin "1") (pinfunction "1_1") (pintype "passive"))
      (node (ref "R17") (pin "1") (pinfunction "1_1") (pintype "passive"))
      (node (ref "R20") (pin "2") (pinfunction "2_2") (pintype "passive"))
      (node (ref "R7") (pin "1") (pinfunction "1_1") (pintype "passive"))
      (node (ref "R9") (pin "1") (pinfunction "1_1") (pintype "passive"))
      (node (ref "REG1117") (pin "2") (pinfunction "VOUT_2") (pintype "power_in"))
      (node (ref "REG1117") (pin "4") (pinfunction "VOUT_4") (pintype "power_in"))
      (node (ref "STM32F103C8") (pin "1") (pinfunction "VBAT_1") (pintype "power_in"))
      (node (ref "STM32F103C8") (pin "24") (pinfunction "VDD_1_24") (pintype "power_in"))
      (node (ref "STM32F103C8") (pin "36") (pinfunction "VDD_2_36") (pintype "power_in"))
      (node (ref "STM32F103C8") (pin "48") (pinfunction "VDD_3_48") (pintype "power_in"))
      (node (ref "SWD") (pin "1") (pinfunction "1_1") (pintype "passive"))
    )
    (net (code "57") (name "VI") (class "Default")
      (node (ref "BAT60J") (pin "C") (pinfunction "C_C") (pintype "passive"))
      (node (ref "C10") (pin "1") (pinfunction "1_1") (pintype "passive"))
      (node (ref "C20") (pin "1") (pinfunction "1_1") (pintype "passive"))
      (node (ref "R13") (pin "2") (pinfunction "2_2") (pintype "passive"))
      (node (ref "R6") (pin "1") (pinfunction "1_1") (pintype "passive"))
      (node (ref "U1") (pin "1") (pinfunction "VI_1") (pintype "power_in"))
      (node (ref "USART") (pin "3") (pinfunction "3_3") (pintype "passive"))
    )
    (net (code "58") (name "unconnected-(STM32F103C8C-PA0-Pad10)") (class "Default")
      (node (ref "STM32F103C8") (pin "10") (pinfunction "PA0_10") (pintype "bidirectional"))
    )
    (net (code "59") (name "unconnected-(STM32F103C8D-PB12-Pad25)") (class "Default")
      (node (ref "STM32F103C8") (pin "25") (pinfunction "PB12_25") (pintype "bidirectional"))
    )
    (net (code "60") (name "unconnected-(STM32F103C8F-PC13-Pad2)") (class "Default")
      (node (ref "STM32F103C8") (pin "2") (pinfunction "PC13_2") (pintype "bidirectional"))
    )
    (net (code "61") (name "unconnected-(STM32F103C8F-PC14-Pad3)") (class "Default")
      (node (ref "STM32F103C8") (pin "3") (pinfunction "PC14_3") (pintype "bidirectional"))
    )
    (net (code "62") (name "unconnected-(STM32F103C8F-PC15-Pad4)") (class "Default")
      (node (ref "STM32F103C8") (pin "4") (pinfunction "PC15_4") (pintype "bidirectional"))
    )
    (net (code "63") (name "unconnected-(U$1-PadGPIO_2)") (class "Default")
      (node (ref "U$1") (pin "GPIO_2") (pinfunction "GPIO_2_GPIO_2") (pintype "bidirectional"))
    )
  )
)
